# Arduino_Environmental_Monitor.net
KiCad netlist of a schematic drawn in EAGLE
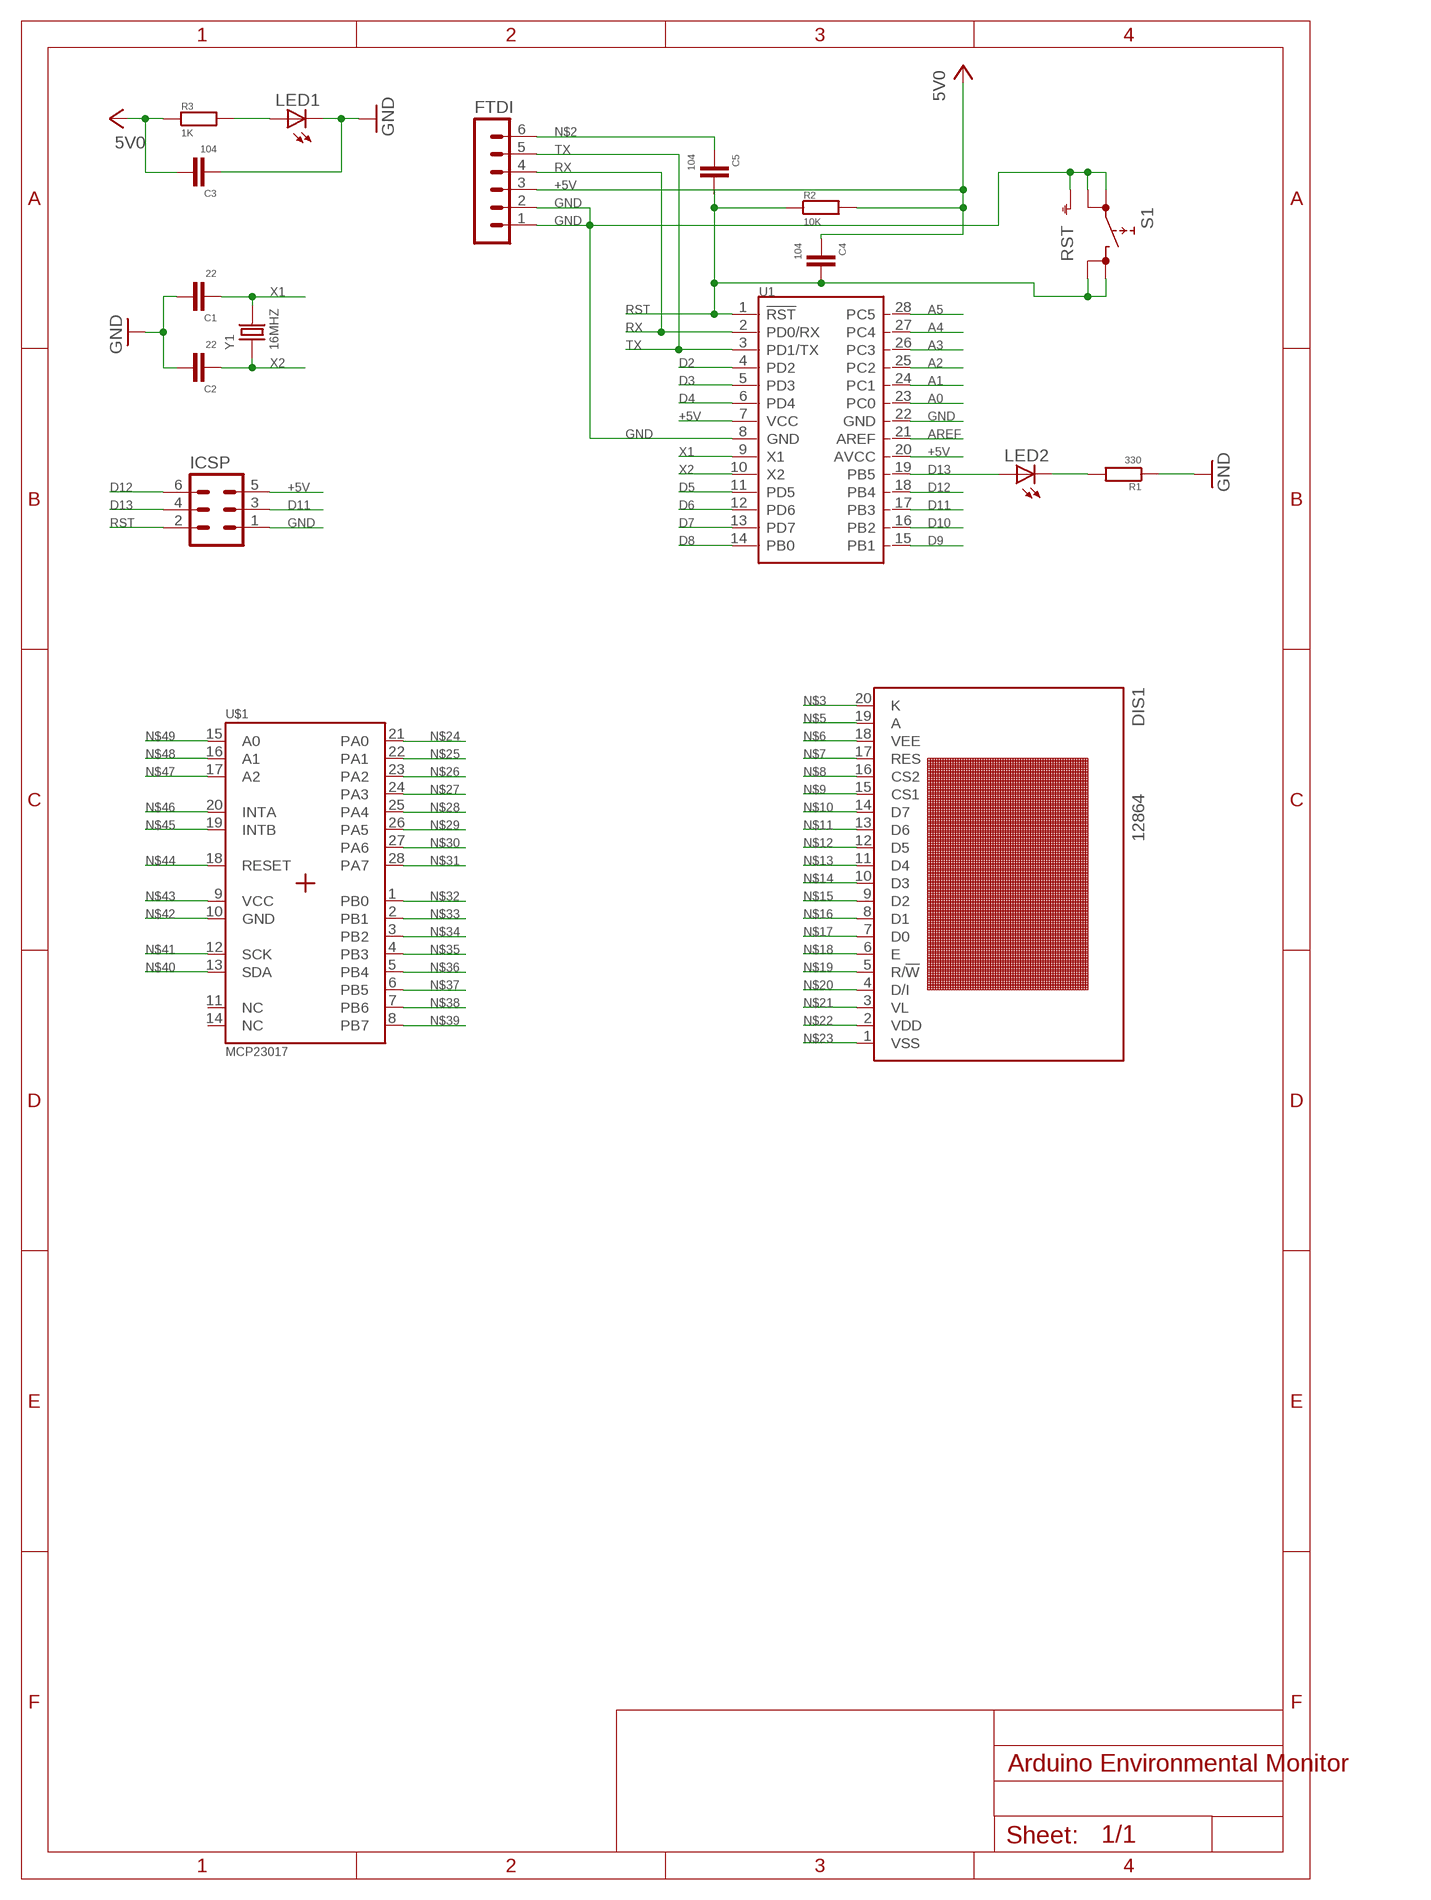
[diagram p0: schematic, sheet 1]

(export (version "E")
  (design (tool "Eeschema 10.0.6"))
  (components
    (comp (ref "C1")
      (value "22")
      (footprint "eagle-import:C0805")
      (libsource (lib "eagle-import") (part "CC0805"))
    )
    (comp (ref "C2")
      (value "22")
      (footprint "eagle-import:C0805")
      (libsource (lib "eagle-import") (part "CC0805"))
    )
    (comp (ref "C3")
      (value "104")
      (footprint "eagle-import:C0805")
      (libsource (lib "eagle-import") (part "CC0805"))
    )
    (comp (ref "C4")
      (value "104")
      (footprint "eagle-import:C0805")
      (libsource (lib "eagle-import") (part "CC0805"))
    )
    (comp (ref "C5")
      (value "104")
      (footprint "eagle-import:C0805")
      (libsource (lib "eagle-import") (part "CC0805"))
    )
    (comp (ref "DIS1")
      (value "12864")
      (footprint "eagle-import:LCD128X64")
      (libsource (lib "eagle-import") (part "LCD128X64"))
    )
    (comp (ref "FTDI")
      (value "MA06-1")
      (footprint "eagle-import:MA06-1")
      (libsource (lib "eagle-import") (part "MA06-1"))
    )
    (comp (ref "ICSP")
      (value "MA03-2")
      (footprint "eagle-import:MA03-2")
      (libsource (lib "eagle-import") (part "MA03-2"))
    )
    (comp (ref "LED1")
      (value "LEDCHIPLED_0805")
      (footprint "eagle-import:CHIPLED_0805")
      (libsource (lib "eagle-import") (part "LEDCHIPLED_0805"))
    )
    (comp (ref "LED2")
      (value "LEDCHIPLED_0805")
      (footprint "eagle-import:CHIPLED_0805")
      (libsource (lib "eagle-import") (part "LEDCHIPLED_0805"))
    )
    (comp (ref "R1")
      (value "330")
      (footprint "eagle-import:R0805")
      (libsource (lib "eagle-import") (part "RR0805"))
    )
    (comp (ref "R2")
      (value "10K")
      (footprint "eagle-import:R0805")
      (libsource (lib "eagle-import") (part "RR0805"))
    )
    (comp (ref "R3")
      (value "1K")
      (footprint "eagle-import:R0805")
      (libsource (lib "eagle-import") (part "RR0805"))
    )
    (comp (ref "S1")
      (value "RST")
      (footprint "eagle-import:SKHMPXE010")
      (libsource (lib "eagle-import") (part "SKHMPE010S"))
    )
    (comp (ref "U$1")
      (value "MCP23017")
      (footprint "eagle-import:SO28W")
      (libsource (lib "eagle-import") (part "MCP23017"))
    )
    (comp (ref "U1")
      (value "MCU-ATMEGA328P-PU(DIP28)")
      (footprint "eagle-import:DIP28-2.54-35.6X13.5MM")
      (fields (field (name "MPN") "ATMEGA328P-PU"))
      (libsource (lib "eagle-import") (part "MCU-ATMEGA328P-PU(DIP28)"))
    )
    (comp (ref "Y1")
      (value "16MHZ")
      (footprint "eagle-import:HC49US")
      (fields (field (name "MPN") "HC-49US    16.000MHz"))
      (libsource (lib "eagle-import") (part "DIP-CRYSTAL-16MHZ-18PF-30PPM-40R(HC49US)"))
    )
  )
  (nets
    (net (code "1") (name "/A0") (class "Default")
      (node (ref "U1") (pin "23") (pinfunction "PC0_23") (pintype "bidirectional"))
    )
    (net (code "2") (name "/A1") (class "Default")
      (node (ref "U1") (pin "24") (pinfunction "PC1_24") (pintype "bidirectional"))
    )
    (net (code "3") (name "/A2") (class "Default")
      (node (ref "U1") (pin "25") (pinfunction "PC2_25") (pintype "bidirectional"))
    )
    (net (code "4") (name "/A3") (class "Default")
      (node (ref "U1") (pin "26") (pinfunction "PC3_26") (pintype "bidirectional"))
    )
    (net (code "5") (name "/A4") (class "Default")
      (node (ref "U1") (pin "27") (pinfunction "PC4_27") (pintype "bidirectional"))
    )
    (net (code "6") (name "/A5") (class "Default")
      (node (ref "U1") (pin "28") (pinfunction "PC5_28") (pintype "bidirectional"))
    )
    (net (code "7") (name "/AREF") (class "Default")
      (node (ref "U1") (pin "21") (pinfunction "AREF_21") (pintype "bidirectional"))
    )
    (net (code "8") (name "/D2") (class "Default")
      (node (ref "U1") (pin "4") (pinfunction "PD2_4") (pintype "bidirectional"))
    )
    (net (code "9") (name "/D3") (class "Default")
      (node (ref "U1") (pin "5") (pinfunction "PD3_5") (pintype "bidirectional"))
    )
    (net (code "10") (name "/D4") (class "Default")
      (node (ref "U1") (pin "6") (pinfunction "PD4_6") (pintype "bidirectional"))
    )
    (net (code "11") (name "/D5") (class "Default")
      (node (ref "U1") (pin "11") (pinfunction "PD5_11") (pintype "bidirectional"))
    )
    (net (code "12") (name "/D6") (class "Default")
      (node (ref "U1") (pin "12") (pinfunction "PD6_12") (pintype "bidirectional"))
    )
    (net (code "13") (name "/D7") (class "Default")
      (node (ref "U1") (pin "13") (pinfunction "PD7_13") (pintype "bidirectional"))
    )
    (net (code "14") (name "/D8") (class "Default")
      (node (ref "U1") (pin "14") (pinfunction "PB0_14") (pintype "bidirectional"))
    )
    (net (code "15") (name "/D9") (class "Default")
      (node (ref "U1") (pin "15") (pinfunction "PB1_15") (pintype "bidirectional"))
    )
    (net (code "16") (name "/D10") (class "Default")
      (node (ref "U1") (pin "16") (pinfunction "PB2_16") (pintype "bidirectional"))
    )
    (net (code "17") (name "/D11") (class "Default")
      (node (ref "ICSP") (pin "3") (pinfunction "3_3") (pintype "passive"))
      (node (ref "U1") (pin "17") (pinfunction "PB3_17") (pintype "bidirectional"))
    )
    (net (code "18") (name "/D12") (class "Default")
      (node (ref "ICSP") (pin "6") (pinfunction "6_6") (pintype "passive"))
      (node (ref "U1") (pin "18") (pinfunction "PB4_18") (pintype "bidirectional"))
    )
    (net (code "19") (name "/D13") (class "Default")
      (node (ref "ICSP") (pin "4") (pinfunction "4_4") (pintype "passive"))
      (node (ref "LED2") (pin "A") (pinfunction "A_A") (pintype "passive"))
      (node (ref "U1") (pin "19") (pinfunction "PB5_19") (pintype "bidirectional"))
    )
    (net (code "20") (name "/N$2") (class "Default")
      (node (ref "C5") (pin "2") (pinfunction "2_2") (pintype "bidirectional"))
      (node (ref "FTDI") (pin "6") (pinfunction "6_6") (pintype "passive"))
    )
    (net (code "21") (name "/N$3") (class "Default")
      (node (ref "DIS1") (pin "20") (pinfunction "K_20") (pintype "passive"))
    )
    (net (code "22") (name "/N$5") (class "Default")
      (node (ref "DIS1") (pin "19") (pinfunction "A_19") (pintype "passive"))
    )
    (net (code "23") (name "/N$6") (class "Default")
      (node (ref "DIS1") (pin "18") (pinfunction "VEE_18") (pintype "output"))
    )
    (net (code "24") (name "/N$7") (class "Default")
      (node (ref "DIS1") (pin "17") (pinfunction "RES_17") (pintype "input"))
    )
    (net (code "25") (name "/N$8") (class "Default")
      (node (ref "DIS1") (pin "16") (pinfunction "CS2_16") (pintype "input"))
    )
    (net (code "26") (name "/N$9") (class "Default")
      (node (ref "DIS1") (pin "15") (pinfunction "CS1_15") (pintype "input"))
    )
    (net (code "27") (name "/N$10") (class "Default")
      (node (ref "DIS1") (pin "14") (pinfunction "D7_14") (pintype "bidirectional"))
    )
    (net (code "28") (name "/N$11") (class "Default")
      (node (ref "DIS1") (pin "13") (pinfunction "D6_13") (pintype "bidirectional"))
    )
    (net (code "29") (name "/N$12") (class "Default")
      (node (ref "DIS1") (pin "12") (pinfunction "D5_12") (pintype "bidirectional"))
    )
    (net (code "30") (name "/N$13") (class "Default")
      (node (ref "DIS1") (pin "11") (pinfunction "D4_11") (pintype "bidirectional"))
    )
    (net (code "31") (name "/N$14") (class "Default")
      (node (ref "DIS1") (pin "10") (pinfunction "D3_10") (pintype "bidirectional"))
    )
    (net (code "32") (name "/N$15") (class "Default")
      (node (ref "DIS1") (pin "9") (pinfunction "D2_9") (pintype "bidirectional"))
    )
    (net (code "33") (name "/N$16") (class "Default")
      (node (ref "DIS1") (pin "8") (pinfunction "D1_8") (pintype "bidirectional"))
    )
    (net (code "34") (name "/N$17") (class "Default")
      (node (ref "DIS1") (pin "7") (pinfunction "D0_7") (pintype "bidirectional"))
    )
    (net (code "35") (name "/N$18") (class "Default")
      (node (ref "DIS1") (pin "6") (pinfunction "E_6") (pintype "input"))
    )
    (net (code "36") (name "/N$19") (class "Default")
      (node (ref "DIS1") (pin "5") (pinfunction "R/~{W}_5") (pintype "input"))
    )
    (net (code "37") (name "/N$20") (class "Default")
      (node (ref "DIS1") (pin "4") (pinfunction "D/I_4") (pintype "input"))
    )
    (net (code "38") (name "/N$21") (class "Default")
      (node (ref "DIS1") (pin "3") (pinfunction "VL_3") (pintype "passive"))
    )
    (net (code "39") (name "/N$22") (class "Default")
      (node (ref "DIS1") (pin "2") (pinfunction "VDD_2") (pintype "power_in"))
    )
    (net (code "40") (name "/N$23") (class "Default")
      (node (ref "DIS1") (pin "1") (pinfunction "VSS_1") (pintype "power_in"))
    )
    (net (code "41") (name "/N$24") (class "Default")
      (node (ref "U$1") (pin "21") (pinfunction "PA0_21") (pintype "bidirectional"))
    )
    (net (code "42") (name "/N$25") (class "Default")
      (node (ref "U$1") (pin "22") (pinfunction "PA1_22") (pintype "bidirectional"))
    )
    (net (code "43") (name "/N$26") (class "Default")
      (node (ref "U$1") (pin "23") (pinfunction "PA2_23") (pintype "bidirectional"))
    )
    (net (code "44") (name "/N$27") (class "Default")
      (node (ref "U$1") (pin "24") (pinfunction "PA3_24") (pintype "bidirectional"))
    )
    (net (code "45") (name "/N$28") (class "Default")
      (node (ref "U$1") (pin "25") (pinfunction "PA4_25") (pintype "bidirectional"))
    )
    (net (code "46") (name "/N$29") (class "Default")
      (node (ref "U$1") (pin "26") (pinfunction "PA5_26") (pintype "bidirectional"))
    )
    (net (code "47") (name "/N$30") (class "Default")
      (node (ref "U$1") (pin "27") (pinfunction "PA6_27") (pintype "bidirectional"))
    )
    (net (code "48") (name "/N$31") (class "Default")
      (node (ref "U$1") (pin "28") (pinfunction "PA7_28") (pintype "bidirectional"))
    )
    (net (code "49") (name "/N$32") (class "Default")
      (node (ref "U$1") (pin "1") (pinfunction "PB0_1") (pintype "bidirectional"))
    )
    (net (code "50") (name "/N$33") (class "Default")
      (node (ref "U$1") (pin "2") (pinfunction "PB1_2") (pintype "bidirectional"))
    )
    (net (code "51") (name "/N$34") (class "Default")
      (node (ref "U$1") (pin "3") (pinfunction "PB2_3") (pintype "bidirectional"))
    )
    (net (code "52") (name "/N$35") (class "Default")
      (node (ref "U$1") (pin "4") (pinfunction "PB3_4") (pintype "bidirectional"))
    )
    (net (code "53") (name "/N$36") (class "Default")
      (node (ref "U$1") (pin "5") (pinfunction "PB4_5") (pintype "bidirectional"))
    )
    (net (code "54") (name "/N$37") (class "Default")
      (node (ref "U$1") (pin "6") (pinfunction "PB5_6") (pintype "bidirectional"))
    )
    (net (code "55") (name "/N$38") (class "Default")
      (node (ref "U$1") (pin "7") (pinfunction "PB6_7") (pintype "bidirectional"))
    )
    (net (code "56") (name "/N$39") (class "Default")
      (node (ref "U$1") (pin "8") (pinfunction "PB7_8") (pintype "bidirectional"))
    )
    (net (code "57") (name "/N$40") (class "Default")
      (node (ref "U$1") (pin "13") (pinfunction "SDA_13") (pintype "bidirectional"))
    )
    (net (code "58") (name "/N$41") (class "Default")
      (node (ref "U$1") (pin "12") (pinfunction "SCK_12") (pintype "bidirectional"))
    )
    (net (code "59") (name "/N$42") (class "Default")
      (node (ref "U$1") (pin "10") (pinfunction "GND_10") (pintype "bidirectional"))
    )
    (net (code "60") (name "/N$43") (class "Default")
      (node (ref "U$1") (pin "9") (pinfunction "VCC_9") (pintype "bidirectional"))
    )
    (net (code "61") (name "/N$44") (class "Default")
      (node (ref "U$1") (pin "18") (pinfunction "RESET_18") (pintype "bidirectional"))
    )
    (net (code "62") (name "/N$45") (class "Default")
      (node (ref "U$1") (pin "19") (pinfunction "INTB_19") (pintype "bidirectional"))
    )
    (net (code "63") (name "/N$46") (class "Default")
      (node (ref "U$1") (pin "20") (pinfunction "INTA_20") (pintype "bidirectional"))
    )
    (net (code "64") (name "/N$47") (class "Default")
      (node (ref "U$1") (pin "17") (pinfunction "A2_17") (pintype "bidirectional"))
    )
    (net (code "65") (name "/N$48") (class "Default")
      (node (ref "U$1") (pin "16") (pinfunction "A1_16") (pintype "bidirectional"))
    )
    (net (code "66") (name "/N$49") (class "Default")
      (node (ref "U$1") (pin "15") (pinfunction "A0_15") (pintype "bidirectional"))
    )
    (net (code "67") (name "/RST") (class "Default")
      (node (ref "C4") (pin "1") (pinfunction "1_1") (pintype "bidirectional"))
      (node (ref "ICSP") (pin "2") (pinfunction "2_2") (pintype "passive"))
      (node (ref "R2") (pin "1") (pinfunction "1_1") (pintype "bidirectional"))
      (node (ref "S1") (pin "3") (pinfunction "2.1_3") (pintype "passive"))
      (node (ref "S1") (pin "4") (pinfunction "2.2_4") (pintype "passive"))
      (node (ref "U1") (pin "1") (pinfunction "~{RST}_1") (pintype "bidirectional"))
    )
    (net (code "68") (name "/RX") (class "Default")
      (node (ref "FTDI") (pin "4") (pinfunction "4_4") (pintype "passive"))
      (node (ref "U1") (pin "2") (pinfunction "PD0/RX_2") (pintype "bidirectional"))
    )
    (net (code "69") (name "/TX") (class "Default")
      (node (ref "FTDI") (pin "5") (pinfunction "5_5") (pintype "passive"))
      (node (ref "U1") (pin "3") (pinfunction "PD1/TX_3") (pintype "bidirectional"))
    )
    (net (code "70") (name "/X1") (class "Default")
      (node (ref "C1") (pin "2") (pinfunction "2_2") (pintype "bidirectional"))
      (node (ref "U1") (pin "9") (pinfunction "X1_9") (pintype "bidirectional"))
      (node (ref "Y1") (pin "2") (pinfunction "2_2") (pintype "passive"))
    )
    (net (code "71") (name "/X2") (class "Default")
      (node (ref "C2") (pin "2") (pinfunction "2_2") (pintype "bidirectional"))
      (node (ref "U1") (pin "10") (pinfunction "X2_10") (pintype "bidirectional"))
      (node (ref "Y1") (pin "1") (pinfunction "1_1") (pintype "passive"))
    )
    (net (code "72") (name "5V0") (class "Default")
      (node (ref "C3") (pin "1") (pinfunction "1_1") (pintype "bidirectional"))
      (node (ref "C4") (pin "2") (pinfunction "2_2") (pintype "bidirectional"))
      (node (ref "FTDI") (pin "3") (pinfunction "3_3") (pintype "passive"))
      (node (ref "ICSP") (pin "5") (pinfunction "5_5") (pintype "passive"))
      (node (ref "R2") (pin "2") (pinfunction "2_2") (pintype "bidirectional"))
      (node (ref "R3") (pin "1") (pinfunction "1_1") (pintype "bidirectional"))
      (node (ref "U1") (pin "20") (pinfunction "AVCC_20") (pintype "bidirectional"))
      (node (ref "U1") (pin "7") (pinfunction "VCC_7") (pintype "bidirectional"))
    )
    (net (code "73") (name "GND") (class "Default")
      (node (ref "C1") (pin "1") (pinfunction "1_1") (pintype "bidirectional"))
      (node (ref "C2") (pin "1") (pinfunction "1_1") (pintype "bidirectional"))
      (node (ref "C3") (pin "2") (pinfunction "2_2") (pintype "bidirectional"))
      (node (ref "FTDI") (pin "1") (pinfunction "1_1") (pintype "passive"))
      (node (ref "FTDI") (pin "2") (pinfunction "2_2") (pintype "passive"))
      (node (ref "ICSP") (pin "1") (pinfunction "1_1") (pintype "passive"))
      (node (ref "LED1") (pin "C") (pinfunction "C_C") (pintype "passive"))
      (node (ref "R1") (pin "1") (pinfunction "1_1") (pintype "bidirectional"))
      (node (ref "S1") (pin "1") (pinfunction "1.1_1") (pintype "passive"))
      (node (ref "S1") (pin "2") (pinfunction "1.2_2") (pintype "passive"))
      (node (ref "S1") (pin "5") (pinfunction "SH_5") (pintype "passive"))
      (node (ref "U1") (pin "22") (pinfunction "GND_22") (pintype "bidirectional"))
      (node (ref "U1") (pin "8") (pinfunction "GND_8") (pintype "bidirectional"))
    )
    (net (code "74") (name "Net-(LED1-PadA)") (class "Default")
      (node (ref "LED1") (pin "A") (pinfunction "A_A") (pintype "passive"))
      (node (ref "R3") (pin "2") (pinfunction "2_2") (pintype "bidirectional"))
    )
    (net (code "75") (name "Net-(LED2-PadC)") (class "Default")
      (node (ref "LED2") (pin "C") (pinfunction "C_C") (pintype "passive"))
      (node (ref "R1") (pin "2") (pinfunction "2_2") (pintype "bidirectional"))
    )
    (net (code "76") (name "unconnected-(C5-Pad1)") (class "Default")
      (node (ref "C5") (pin "1") (pinfunction "1_1") (pintype "bidirectional"))
    )
    (net (code "77") (name "unconnected-(U$1-NC-Pad11)") (class "Default")
      (node (ref "U$1") (pin "11") (pinfunction "NC_11") (pintype "bidirectional"))
    )
    (net (code "78") (name "unconnected-(U$1-NC-Pad14)") (class "Default")
      (node (ref "U$1") (pin "14") (pinfunction "NC_14") (pintype "bidirectional"))
    )
  )
)
